# tea_maker.net
KiCad netlist of a schematic drawn in EAGLE
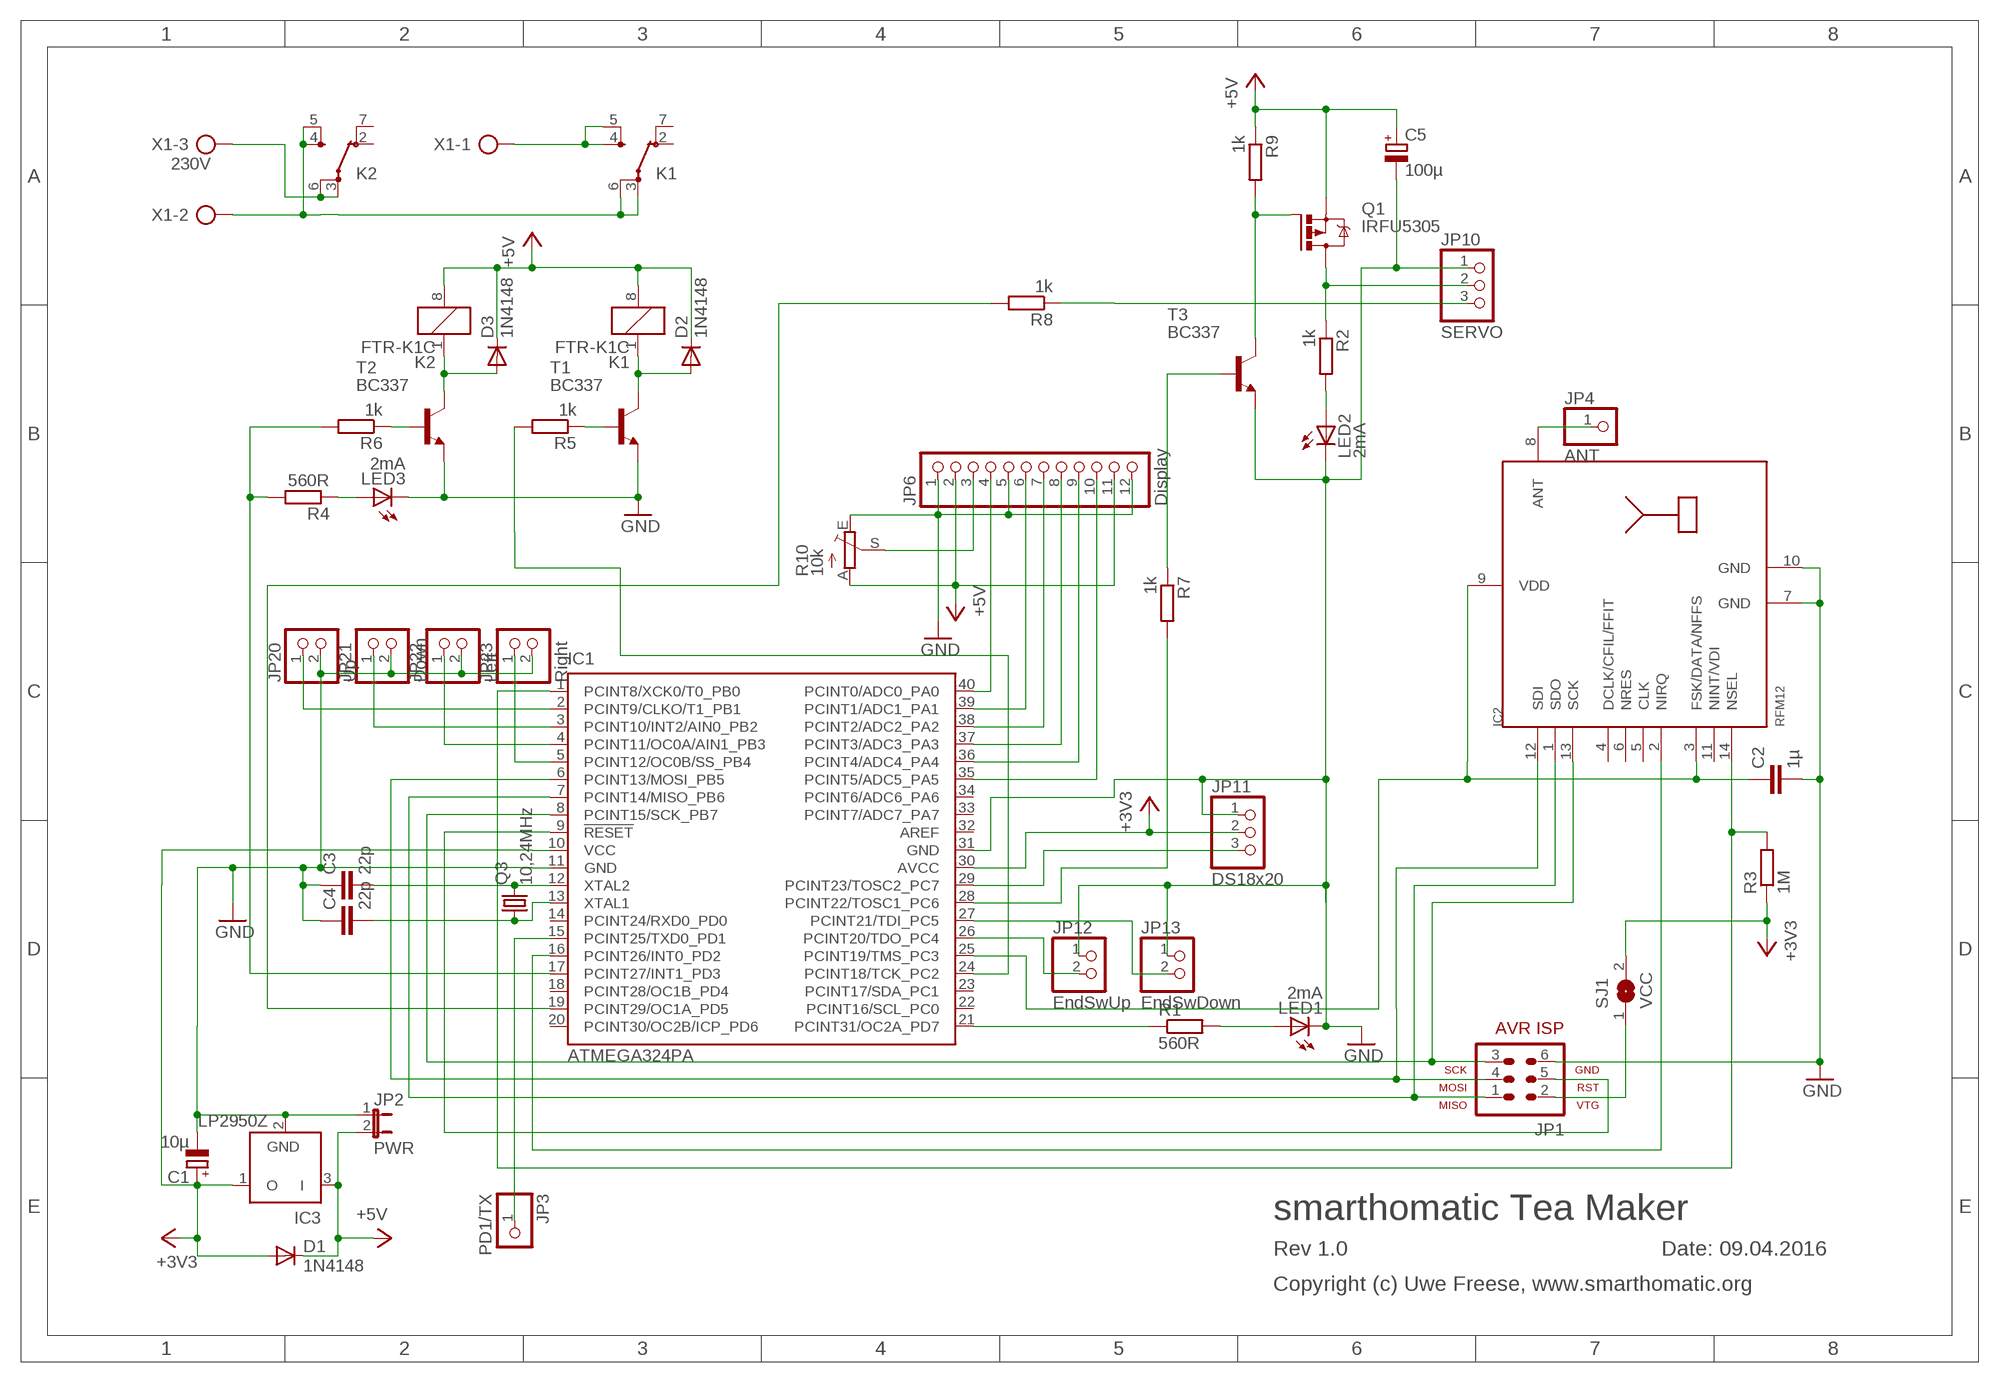
[diagram p0: schematic, sheet 1]

(export (version "E")
  (design (tool "Eeschema 10.0.6"))
  (components
    (comp (ref "C1")
      (value "10µ")
      (footprint "eagle-import:E1,8-4")
      (libsource (lib "eagle-import") (part "CPOL-EUE1.8-4"))
    )
    (comp (ref "C2")
      (value "1µ")
      (footprint "eagle-import:C5B3.5")
      (libsource (lib "eagle-import") (part "C5/3.5"))
    )
    (comp (ref "C3")
      (value "22p")
      (footprint "eagle-import:C025-024X044")
      (libsource (lib "eagle-import") (part "C-EU025-024X044"))
    )
    (comp (ref "C4")
      (value "22p")
      (footprint "eagle-import:C025-024X044")
      (libsource (lib "eagle-import") (part "C-EU025-024X044"))
    )
    (comp (ref "C5")
      (value "100µ")
      (footprint "eagle-import:E2,5-7")
      (libsource (lib "eagle-import") (part "CPOL-EUE2.5-7"))
    )
    (comp (ref "D1")
      (value "1N4148")
      (footprint "eagle-import:DO35-7")
      (libsource (lib "eagle-import") (part "1N4148DO35-7"))
    )
    (comp (ref "D2")
      (value "1N4148")
      (footprint "eagle-import:DO35-7")
      (libsource (lib "eagle-import") (part "1N4148DO35-7"))
    )
    (comp (ref "D3")
      (value "1N4148")
      (footprint "eagle-import:DO35-7")
      (libsource (lib "eagle-import") (part "1N4148DO35-7"))
    )
    (comp (ref "IC1")
      (value "ATMEGA324PA")
      (footprint "eagle-import:DIL40")
      (fields (field (name "MPN") "ATMEGA644V-10PU"))
      (libsource (lib "eagle-import") (part "ATMEGA644-PU10"))
    )
    (comp (ref "IC2")
      (value "RFM12")
      (footprint "eagle-import:RFM")
      (libsource (lib "eagle-import") (part "RFM12"))
    )
    (comp (ref "IC3")
      (value "LP2950Z")
      (footprint "eagle-import:TO92")
      (libsource (lib "eagle-import") (part "LP2950Z"))
    )
    (comp (ref "JP1")
      (value "AVR-ISP-6")
      (footprint "eagle-import:AVR-ISP-6")
      (libsource (lib "eagle-import") (part "AVR-ISP-6"))
    )
    (comp (ref "JP2")
      (value "PWR")
      (footprint "eagle-import:JP1")
      (libsource (lib "eagle-import") (part "JP1E"))
    )
    (comp (ref "JP3")
      (value "PD1/TX")
      (footprint "eagle-import:1X01")
      (libsource (lib "eagle-import") (part "PINHD-1X1"))
    )
    (comp (ref "JP4")
      (value "ANT")
      (footprint "eagle-import:1X01")
      (libsource (lib "eagle-import") (part "PINHD-1X1"))
    )
    (comp (ref "JP6")
      (value "Display")
      (footprint "eagle-import:1X12")
      (libsource (lib "eagle-import") (part "PINHD-1X12"))
    )
    (comp (ref "JP10")
      (value "SERVO")
      (footprint "eagle-import:1X03")
      (libsource (lib "eagle-import") (part "PINHD-1X3"))
    )
    (comp (ref "JP11")
      (value "DS18x20")
      (footprint "eagle-import:1X03")
      (libsource (lib "eagle-import") (part "PINHD-1X3"))
    )
    (comp (ref "JP12")
      (value "EndSwUp")
      (footprint "eagle-import:1X02")
      (libsource (lib "eagle-import") (part "PINHD-1X2"))
    )
    (comp (ref "JP13")
      (value "EndSwDown")
      (footprint "eagle-import:1X02")
      (libsource (lib "eagle-import") (part "PINHD-1X2"))
    )
    (comp (ref "JP20")
      (value "Up")
      (footprint "eagle-import:1X02")
      (libsource (lib "eagle-import") (part "PINHD-1X2"))
    )
    (comp (ref "JP21")
      (value "Down")
      (footprint "eagle-import:1X02")
      (libsource (lib "eagle-import") (part "PINHD-1X2"))
    )
    (comp (ref "JP22")
      (value "Left")
      (footprint "eagle-import:1X02")
      (libsource (lib "eagle-import") (part "PINHD-1X2"))
    )
    (comp (ref "JP23")
      (value "Right")
      (footprint "eagle-import:1X02")
      (libsource (lib "eagle-import") (part "PINHD-1X2"))
    )
    (comp (ref "K1")
      (value "FTR-K1C")
      (footprint "eagle-import:FTR-K1C")
      (libsource (lib "eagle-import") (part "FTR-K1C"))
    )
    (comp (ref "K2")
      (value "FTR-K1C")
      (footprint "eagle-import:FTR-K1C")
      (libsource (lib "eagle-import") (part "FTR-K1C"))
    )
    (comp (ref "LED1")
      (value "2mA")
      (footprint "eagle-import:LED3MM")
      (libsource (lib "eagle-import") (part "LED3MM"))
    )
    (comp (ref "LED2")
      (value "2mA")
      (footprint "eagle-import:LED3MM")
      (libsource (lib "eagle-import") (part "LED3MM"))
    )
    (comp (ref "LED3")
      (value "2mA")
      (footprint "eagle-import:LED3MM")
      (libsource (lib "eagle-import") (part "LED3MM"))
    )
    (comp (ref "Q1")
      (value "IRFU5305")
      (footprint "eagle-import:I-PAK_TO251AA")
      (libsource (lib "eagle-import") (part "IRF?5305U"))
    )
    (comp (ref "Q3")
      (value "10,24MHz")
      (footprint "eagle-import:HC49_S")
      (libsource (lib "eagle-import") (part "CRYSTALHC49S"))
    )
    (comp (ref "R1")
      (value "560R")
      (footprint "eagle-import:0207_7")
      (libsource (lib "eagle-import") (part "R-EU_0207/7"))
    )
    (comp (ref "R2")
      (value "1k")
      (footprint "eagle-import:0207_7")
      (libsource (lib "eagle-import") (part "R-EU_0207/7"))
    )
    (comp (ref "R3")
      (value "1M")
      (footprint "eagle-import:0207_7")
      (libsource (lib "eagle-import") (part "R-EU_0207/7"))
    )
    (comp (ref "R4")
      (value "560R")
      (footprint "eagle-import:0207_7")
      (libsource (lib "eagle-import") (part "R-EU_0207/7"))
    )
    (comp (ref "R5")
      (value "1k")
      (footprint "eagle-import:0207_7")
      (libsource (lib "eagle-import") (part "R-EU_0207/7"))
    )
    (comp (ref "R6")
      (value "1k")
      (footprint "eagle-import:0207_7")
      (libsource (lib "eagle-import") (part "R-EU_0207/7"))
    )
    (comp (ref "R7")
      (value "1k")
      (footprint "eagle-import:0207_7")
      (libsource (lib "eagle-import") (part "R-EU_0207/7"))
    )
    (comp (ref "R8")
      (value "1k")
      (footprint "eagle-import:0207_7")
      (libsource (lib "eagle-import") (part "R-EU_0207/7"))
    )
    (comp (ref "R9")
      (value "1k")
      (footprint "eagle-import:0207_7")
      (libsource (lib "eagle-import") (part "R-EU_0207/7"))
    )
    (comp (ref "R10")
      (value "10k")
      (footprint "eagle-import:PT-10S")
      (libsource (lib "eagle-import") (part "TRIM_EU-PT10S"))
    )
    (comp (ref "SJ1")
      (value "VCC")
      (footprint "eagle-import:SJ")
      (libsource (lib "eagle-import") (part "SJ"))
    )
    (comp (ref "T1")
      (value "BC337")
      (footprint "eagle-import:TO92")
      (libsource (lib "eagle-import") (part "BC337"))
    )
    (comp (ref "T2")
      (value "BC337")
      (footprint "eagle-import:TO92")
      (libsource (lib "eagle-import") (part "BC337"))
    )
    (comp (ref "T3")
      (value "BC337")
      (footprint "eagle-import:TO92")
      (libsource (lib "eagle-import") (part "BC337"))
    )
    (comp (ref "X1")
      (value "230V")
      (footprint "eagle-import:AK500_3")
      (libsource (lib "eagle-import") (part "AK500/3"))
    )
  )
  (nets
    (net (code "1") (name "+3V3") (class "Default")
      (node (ref "C1") (pin "+") (pinfunction "+_+") (pintype "passive"))
      (node (ref "D1") (pin "A") (pinfunction "A_A") (pintype "passive"))
      (node (ref "IC1") (pin "10") (pinfunction "VCC_10") (pintype "power_in"))
      (node (ref "IC1") (pin "30") (pinfunction "AVCC_30") (pintype "power_in"))
      (node (ref "IC3") (pin "1") (pinfunction "O_1") (pintype "input"))
      (node (ref "JP11") (pin "2") (pinfunction "2_2") (pintype "passive"))
      (node (ref "R3") (pin "1") (pinfunction "1_1") (pintype "passive"))
      (node (ref "SJ1") (pin "2") (pinfunction "2_2") (pintype "passive"))
    )
    (net (code "2") (name "+5V") (class "Default")
      (node (ref "C5") (pin "+") (pinfunction "+_+") (pintype "passive"))
      (node (ref "D1") (pin "C") (pinfunction "C_C") (pintype "passive"))
      (node (ref "D2") (pin "C") (pinfunction "C_C") (pintype "passive"))
      (node (ref "D3") (pin "C") (pinfunction "C_C") (pintype "passive"))
      (node (ref "IC3") (pin "3") (pinfunction "I_3") (pintype "input"))
      (node (ref "JP2") (pin "2") (pinfunction "2_2") (pintype "passive"))
      (node (ref "JP6") (pin "11") (pinfunction "11_11") (pintype "passive"))
      (node (ref "JP6") (pin "2") (pinfunction "2_2") (pintype "passive"))
      (node (ref "K1") (pin "8") (pinfunction "2_8") (pintype "passive"))
      (node (ref "K2") (pin "8") (pinfunction "2_8") (pintype "passive"))
      (node (ref "Q1") (pin "3") (pinfunction "S_3") (pintype "passive"))
      (node (ref "R10") (pin "A") (pinfunction "A_A") (pintype "passive"))
      (node (ref "R9") (pin "1") (pinfunction "1_1") (pintype "passive"))
    )
    (net (code "3") (name "GND") (class "Default")
      (node (ref "C1") (pin "-") (pinfunction "-_-") (pintype "passive"))
      (node (ref "C2") (pin "2") (pinfunction "2_2") (pintype "passive"))
      (node (ref "C3") (pin "1") (pinfunction "1_1") (pintype "passive"))
      (node (ref "C4") (pin "1") (pinfunction "1_1") (pintype "passive"))
      (node (ref "C5") (pin "-") (pinfunction "-_-") (pintype "passive"))
      (node (ref "IC1") (pin "11") (pinfunction "GND_11") (pintype "power_in"))
      (node (ref "IC1") (pin "31") (pinfunction "GND_31") (pintype "power_in"))
      (node (ref "IC2") (pin "10") (pinfunction "GND_10") (pintype "power_in"))
      (node (ref "IC2") (pin "7") (pinfunction "GND_7") (pintype "power_in"))
      (node (ref "IC3") (pin "2") (pinfunction "GND_2") (pintype "power_in"))
      (node (ref "JP1") (pin "6") (pinfunction "6_6") (pintype "passive"))
      (node (ref "JP10") (pin "1") (pinfunction "1_1") (pintype "passive"))
      (node (ref "JP11") (pin "1") (pinfunction "1_1") (pintype "passive"))
      (node (ref "JP12") (pin "1") (pinfunction "1_1") (pintype "passive"))
      (node (ref "JP13") (pin "1") (pinfunction "1_1") (pintype "passive"))
      (node (ref "JP2") (pin "1") (pinfunction "1_1") (pintype "passive"))
      (node (ref "JP20") (pin "2") (pinfunction "2_2") (pintype "passive"))
      (node (ref "JP21") (pin "2") (pinfunction "2_2") (pintype "passive"))
      (node (ref "JP22") (pin "2") (pinfunction "2_2") (pintype "passive"))
      (node (ref "JP23") (pin "2") (pinfunction "2_2") (pintype "passive"))
      (node (ref "JP6") (pin "1") (pinfunction "1_1") (pintype "passive"))
      (node (ref "JP6") (pin "12") (pinfunction "12_12") (pintype "passive"))
      (node (ref "JP6") (pin "5") (pinfunction "5_5") (pintype "passive"))
      (node (ref "LED1") (pin "K") (pinfunction "C_K") (pintype "passive"))
      (node (ref "LED2") (pin "K") (pinfunction "C_K") (pintype "passive"))
      (node (ref "LED3") (pin "K") (pinfunction "C_K") (pintype "passive"))
      (node (ref "R10") (pin "E") (pinfunction "E_E") (pintype "passive"))
      (node (ref "T1") (pin "1") (pinfunction "E_1") (pintype "passive"))
      (node (ref "T2") (pin "1") (pinfunction "E_1") (pintype "passive"))
      (node (ref "T3") (pin "1") (pinfunction "E_1") (pintype "passive"))
    )
    (net (code "4") (name "Net-(IC1-PCINT0{slash}ADC0_PA0)") (class "Default")
      (node (ref "IC1") (pin "40") (pinfunction "PCINT0/ADC0_PA0_40") (pintype "bidirectional"))
      (node (ref "JP6") (pin "4") (pinfunction "4_4") (pintype "passive"))
    )
    (net (code "5") (name "Net-(IC1-PCINT1{slash}ADC1_PA1)") (class "Default")
      (node (ref "IC1") (pin "39") (pinfunction "PCINT1/ADC1_PA1_39") (pintype "bidirectional"))
      (node (ref "JP6") (pin "6") (pinfunction "6_6") (pintype "passive"))
    )
    (net (code "6") (name "Net-(IC1-PCINT2{slash}ADC2_PA2)") (class "Default")
      (node (ref "IC1") (pin "38") (pinfunction "PCINT2/ADC2_PA2_38") (pintype "bidirectional"))
      (node (ref "JP6") (pin "7") (pinfunction "7_7") (pintype "passive"))
    )
    (net (code "7") (name "Net-(IC1-PCINT3{slash}ADC3_PA3)") (class "Default")
      (node (ref "IC1") (pin "37") (pinfunction "PCINT3/ADC3_PA3_37") (pintype "bidirectional"))
      (node (ref "JP6") (pin "8") (pinfunction "8_8") (pintype "passive"))
    )
    (net (code "8") (name "Net-(IC1-PCINT4{slash}ADC4_PA4)") (class "Default")
      (node (ref "IC1") (pin "36") (pinfunction "PCINT4/ADC4_PA4_36") (pintype "bidirectional"))
      (node (ref "JP6") (pin "9") (pinfunction "9_9") (pintype "passive"))
    )
    (net (code "9") (name "Net-(IC1-PCINT5{slash}ADC5_PA5)") (class "Default")
      (node (ref "IC1") (pin "35") (pinfunction "PCINT5/ADC5_PA5_35") (pintype "bidirectional"))
      (node (ref "JP6") (pin "10") (pinfunction "10_10") (pintype "passive"))
    )
    (net (code "10") (name "Net-(IC1-PCINT8{slash}XCK0{slash}T0_PB0)") (class "Default")
      (node (ref "IC1") (pin "1") (pinfunction "PCINT8/XCK0/T0_PB0_1") (pintype "bidirectional"))
      (node (ref "IC2") (pin "14") (pinfunction "NSEL_14") (pintype "bidirectional"))
      (node (ref "R3") (pin "2") (pinfunction "2_2") (pintype "passive"))
    )
    (net (code "11") (name "Net-(IC1-PCINT9{slash}CLKO{slash}T1_PB1)") (class "Default")
      (node (ref "IC1") (pin "2") (pinfunction "PCINT9/CLKO/T1_PB1_2") (pintype "bidirectional"))
      (node (ref "JP20") (pin "1") (pinfunction "1_1") (pintype "passive"))
    )
    (net (code "12") (name "Net-(IC1-PCINT10{slash}INT2{slash}AIN0_PB2)") (class "Default")
      (node (ref "IC1") (pin "3") (pinfunction "PCINT10/INT2/AIN0_PB2_3") (pintype "bidirectional"))
      (node (ref "JP21") (pin "1") (pinfunction "1_1") (pintype "passive"))
    )
    (net (code "13") (name "Net-(IC1-PCINT11{slash}OC0A{slash}AIN1_PB3)") (class "Default")
      (node (ref "IC1") (pin "4") (pinfunction "PCINT11/OC0A/AIN1_PB3_4") (pintype "bidirectional"))
      (node (ref "JP22") (pin "1") (pinfunction "1_1") (pintype "passive"))
    )
    (net (code "14") (name "Net-(IC1-PCINT12{slash}OC0B{slash}SS_PB4)") (class "Default")
      (node (ref "IC1") (pin "5") (pinfunction "PCINT12/OC0B/SS_PB4_5") (pintype "bidirectional"))
      (node (ref "JP23") (pin "1") (pinfunction "1_1") (pintype "passive"))
    )
    (net (code "15") (name "Net-(IC1-PCINT13{slash}MOSI_PB5)") (class "Default")
      (node (ref "IC1") (pin "6") (pinfunction "PCINT13/MOSI_PB5_6") (pintype "bidirectional"))
      (node (ref "IC2") (pin "12") (pinfunction "SDI_12") (pintype "bidirectional"))
      (node (ref "JP1") (pin "4") (pinfunction "4_4") (pintype "passive"))
    )
    (net (code "16") (name "Net-(IC1-PCINT14{slash}MISO_PB6)") (class "Default")
      (node (ref "IC1") (pin "7") (pinfunction "PCINT14/MISO_PB6_7") (pintype "bidirectional"))
      (node (ref "IC2") (pin "1") (pinfunction "SDO_1") (pintype "bidirectional"))
      (node (ref "JP1") (pin "1") (pinfunction "1_1") (pintype "passive"))
    )
    (net (code "17") (name "Net-(IC1-PCINT15{slash}SCK_PB7)") (class "Default")
      (node (ref "IC1") (pin "8") (pinfunction "PCINT15/SCK_PB7_8") (pintype "bidirectional"))
      (node (ref "IC2") (pin "13") (pinfunction "SCK_13") (pintype "bidirectional"))
      (node (ref "JP1") (pin "3") (pinfunction "3_3") (pintype "passive"))
    )
    (net (code "18") (name "Net-(IC1-PCINT18{slash}TCK_PC2)") (class "Default")
      (node (ref "IC1") (pin "24") (pinfunction "PCINT18/TCK_PC2_24") (pintype "bidirectional"))
      (node (ref "R5") (pin "2") (pinfunction "2_2") (pintype "passive"))
    )
    (net (code "19") (name "Net-(IC1-PCINT19{slash}TMS_PC3)") (class "Default")
      (node (ref "C2") (pin "1") (pinfunction "1_1") (pintype "passive"))
      (node (ref "IC1") (pin "25") (pinfunction "PCINT19/TMS_PC3_25") (pintype "bidirectional"))
      (node (ref "IC2") (pin "3") (pinfunction "FSK/DATA/NFFS_3") (pintype "bidirectional"))
      (node (ref "IC2") (pin "9") (pinfunction "VDD_9") (pintype "power_in"))
    )
    (net (code "20") (name "Net-(IC1-PCINT20{slash}TDO_PC4)") (class "Default")
      (node (ref "IC1") (pin "26") (pinfunction "PCINT20/TDO_PC4_26") (pintype "bidirectional"))
      (node (ref "JP12") (pin "2") (pinfunction "2_2") (pintype "passive"))
    )
    (net (code "21") (name "Net-(IC1-PCINT21{slash}TDI_PC5)") (class "Default")
      (node (ref "IC1") (pin "27") (pinfunction "PCINT21/TDI_PC5_27") (pintype "bidirectional"))
      (node (ref "JP13") (pin "2") (pinfunction "2_2") (pintype "passive"))
    )
    (net (code "22") (name "Net-(IC1-PCINT22{slash}TOSC1_PC6)") (class "Default")
      (node (ref "IC1") (pin "28") (pinfunction "PCINT22/TOSC1_PC6_28") (pintype "bidirectional"))
      (node (ref "R7") (pin "2") (pinfunction "2_2") (pintype "passive"))
    )
    (net (code "23") (name "Net-(IC1-PCINT23{slash}TOSC2_PC7)") (class "Default")
      (node (ref "IC1") (pin "29") (pinfunction "PCINT23/TOSC2_PC7_29") (pintype "bidirectional"))
      (node (ref "JP11") (pin "3") (pinfunction "3_3") (pintype "passive"))
    )
    (net (code "24") (name "Net-(IC1-PCINT25{slash}TXD0_PD1)") (class "Default")
      (node (ref "IC1") (pin "15") (pinfunction "PCINT25/TXD0_PD1_15") (pintype "bidirectional"))
      (node (ref "JP3") (pin "1") (pinfunction "1_1") (pintype "passive"))
    )
    (net (code "25") (name "Net-(IC1-PCINT26{slash}INT0_PD2)") (class "Default")
      (node (ref "IC1") (pin "16") (pinfunction "PCINT26/INT0_PD2_16") (pintype "bidirectional"))
      (node (ref "IC2") (pin "2") (pinfunction "NIRQ_2") (pintype "bidirectional"))
    )
    (net (code "26") (name "Net-(IC1-PCINT27{slash}INT1_PD3)") (class "Default")
      (node (ref "IC1") (pin "17") (pinfunction "PCINT27/INT1_PD3_17") (pintype "bidirectional"))
      (node (ref "R4") (pin "2") (pinfunction "2_2") (pintype "passive"))
      (node (ref "R6") (pin "2") (pinfunction "2_2") (pintype "passive"))
    )
    (net (code "27") (name "Net-(IC1-PCINT29{slash}OC1A_PD5)") (class "Default")
      (node (ref "IC1") (pin "19") (pinfunction "PCINT29/OC1A_PD5_19") (pintype "bidirectional"))
      (node (ref "R8") (pin "2") (pinfunction "2_2") (pintype "passive"))
    )
    (net (code "28") (name "Net-(IC1-PCINT31{slash}OC2A_PD7)") (class "Default")
      (node (ref "IC1") (pin "21") (pinfunction "PCINT31/OC2A_PD7_21") (pintype "bidirectional"))
      (node (ref "R1") (pin "1") (pinfunction "1_1") (pintype "passive"))
    )
    (net (code "29") (name "Net-(IC1-XTAL1)") (class "Default")
      (node (ref "C4") (pin "2") (pinfunction "2_2") (pintype "passive"))
      (node (ref "IC1") (pin "13") (pinfunction "XTAL1_13") (pintype "input"))
      (node (ref "Q3") (pin "1") (pinfunction "1_1") (pintype "passive"))
    )
    (net (code "30") (name "Net-(IC1-XTAL2)") (class "Default")
      (node (ref "C3") (pin "2") (pinfunction "2_2") (pintype "passive"))
      (node (ref "IC1") (pin "12") (pinfunction "XTAL2_12") (pintype "output"))
      (node (ref "Q3") (pin "2") (pinfunction "2_2") (pintype "passive"))
    )
    (net (code "31") (name "Net-(IC1-~{RESET})") (class "Default")
      (node (ref "IC1") (pin "9") (pinfunction "~{RESET}_9") (pintype "input"))
      (node (ref "JP1") (pin "5") (pinfunction "5_5") (pintype "passive"))
    )
    (net (code "32") (name "Net-(IC2-ANT)") (class "Default")
      (node (ref "IC2") (pin "8") (pinfunction "ANT_8") (pintype "output"))
      (node (ref "JP4") (pin "1") (pinfunction "1_1") (pintype "passive"))
    )
    (net (code "33") (name "Net-(JP1-Pad2)") (class "Default")
      (node (ref "JP1") (pin "2") (pinfunction "2_2") (pintype "passive"))
      (node (ref "SJ1") (pin "1") (pinfunction "1_1") (pintype "passive"))
    )
    (net (code "34") (name "Net-(JP6-Pad3)") (class "Default")
      (node (ref "JP6") (pin "3") (pinfunction "3_3") (pintype "passive"))
      (node (ref "R10") (pin "S") (pinfunction "S_S") (pintype "passive"))
    )
    (net (code "35") (name "Net-(JP10-Pad3)") (class "Default")
      (node (ref "JP10") (pin "3") (pinfunction "3_3") (pintype "passive"))
      (node (ref "R8") (pin "1") (pinfunction "1_1") (pintype "passive"))
    )
    (net (code "36") (name "Net-(K1A-PA)") (class "Default")
      (node (ref "K1") (pin "3") (pinfunction "PA_3") (pintype "passive"))
      (node (ref "K1") (pin "6") (pinfunction "PB_6") (pintype "passive"))
      (node (ref "K2") (pin "4") (pinfunction "SA_4") (pintype "passive"))
      (node (ref "K2") (pin "5") (pinfunction "SB_5") (pintype "passive"))
      (node (ref "X1") (pin "2") (pinfunction "KL_2") (pintype "passive"))
    )
    (net (code "37") (name "Net-(K1A-SA)") (class "Default")
      (node (ref "K1") (pin "4") (pinfunction "SA_4") (pintype "passive"))
      (node (ref "K1") (pin "5") (pinfunction "SB_5") (pintype "passive"))
      (node (ref "X1") (pin "1") (pinfunction "KL_1") (pintype "passive"))
    )
    (net (code "38") (name "Net-(K2A-PA)") (class "Default")
      (node (ref "K2") (pin "3") (pinfunction "PA_3") (pintype "passive"))
      (node (ref "K2") (pin "6") (pinfunction "PB_6") (pintype "passive"))
      (node (ref "X1") (pin "3") (pinfunction "KL_3") (pintype "passive"))
    )
    (net (code "39") (name "Net-(LED1-PadA)") (class "Default")
      (node (ref "LED1") (pin "A") (pinfunction "A_A") (pintype "passive"))
      (node (ref "R1") (pin "2") (pinfunction "2_2") (pintype "passive"))
    )
    (net (code "40") (name "Net-(LED2-PadA)") (class "Default")
      (node (ref "LED2") (pin "A") (pinfunction "A_A") (pintype "passive"))
      (node (ref "R2") (pin "2") (pinfunction "2_2") (pintype "passive"))
    )
    (net (code "41") (name "Net-(LED3-PadA)") (class "Default")
      (node (ref "LED3") (pin "A") (pinfunction "A_A") (pintype "passive"))
      (node (ref "R4") (pin "1") (pinfunction "1_1") (pintype "passive"))
    )
    (net (code "42") (name "Net-(Q1-D)") (class "Default")
      (node (ref "JP10") (pin "2") (pinfunction "2_2") (pintype "passive"))
      (node (ref "Q1") (pin "2") (pinfunction "D_2") (pintype "passive"))
      (node (ref "R2") (pin "1") (pinfunction "1_1") (pintype "passive"))
    )
    (net (code "43") (name "Net-(Q1-G)") (class "Default")
      (node (ref "Q1") (pin "1") (pinfunction "G_1") (pintype "passive"))
      (node (ref "R9") (pin "2") (pinfunction "2_2") (pintype "passive"))
      (node (ref "T3") (pin "3") (pinfunction "C_3") (pintype "passive"))
    )
    (net (code "44") (name "Net-(T1-B)") (class "Default")
      (node (ref "R5") (pin "1") (pinfunction "1_1") (pintype "passive"))
      (node (ref "T1") (pin "2") (pinfunction "B_2") (pintype "passive"))
    )
    (net (code "45") (name "Net-(T1-C)") (class "Default")
      (node (ref "D2") (pin "A") (pinfunction "A_A") (pintype "passive"))
      (node (ref "K1") (pin "1") (pinfunction "1_1") (pintype "passive"))
      (node (ref "T1") (pin "3") (pinfunction "C_3") (pintype "passive"))
    )
    (net (code "46") (name "Net-(T2-B)") (class "Default")
      (node (ref "R6") (pin "1") (pinfunction "1_1") (pintype "passive"))
      (node (ref "T2") (pin "2") (pinfunction "B_2") (pintype "passive"))
    )
    (net (code "47") (name "Net-(T2-C)") (class "Default")
      (node (ref "D3") (pin "A") (pinfunction "A_A") (pintype "passive"))
      (node (ref "K2") (pin "1") (pinfunction "1_1") (pintype "passive"))
      (node (ref "T2") (pin "3") (pinfunction "C_3") (pintype "passive"))
    )
    (net (code "48") (name "Net-(T3-B)") (class "Default")
      (node (ref "R7") (pin "1") (pinfunction "1_1") (pintype "passive"))
      (node (ref "T3") (pin "2") (pinfunction "B_2") (pintype "passive"))
    )
    (net (code "49") (name "unconnected-(IC1-AREF-Pad32)") (class "Default")
      (node (ref "IC1") (pin "32") (pinfunction "AREF_32") (pintype "passive"))
    )
    (net (code "50") (name "unconnected-(IC1-PCINT6{slash}ADC6_PA6-Pad34)") (class "Default")
      (node (ref "IC1") (pin "34") (pinfunction "PCINT6/ADC6_PA6_34") (pintype "bidirectional"))
    )
    (net (code "51") (name "unconnected-(IC1-PCINT7{slash}ADC7_PA7-Pad33)") (class "Default")
      (node (ref "IC1") (pin "33") (pinfunction "PCINT7/ADC7_PA7_33") (pintype "bidirectional"))
    )
    (net (code "52") (name "unconnected-(IC1-PCINT16{slash}SCL_PC0-Pad22)") (class "Default")
      (node (ref "IC1") (pin "22") (pinfunction "PCINT16/SCL_PC0_22") (pintype "bidirectional"))
    )
    (net (code "53") (name "unconnected-(IC1-PCINT17{slash}SDA_PC1-Pad23)") (class "Default")
      (node (ref "IC1") (pin "23") (pinfunction "PCINT17/SDA_PC1_23") (pintype "bidirectional"))
    )
    (net (code "54") (name "unconnected-(IC1-PCINT24{slash}RXD0_PD0-Pad14)") (class "Default")
      (node (ref "IC1") (pin "14") (pinfunction "PCINT24/RXD0_PD0_14") (pintype "bidirectional"))
    )
    (net (code "55") (name "unconnected-(IC1-PCINT28{slash}OC1B_PD4-Pad18)") (class "Default")
      (node (ref "IC1") (pin "18") (pinfunction "PCINT28/OC1B_PD4_18") (pintype "bidirectional"))
    )
    (net (code "56") (name "unconnected-(IC1-PCINT30{slash}OC2B{slash}ICP_PD6-Pad20)") (class "Default")
      (node (ref "IC1") (pin "20") (pinfunction "PCINT30/OC2B/ICP_PD6_20") (pintype "bidirectional"))
    )
    (net (code "57") (name "unconnected-(IC2-CLK-Pad5)") (class "Default")
      (node (ref "IC2") (pin "5") (pinfunction "CLK_5") (pintype "bidirectional"))
    )
    (net (code "58") (name "unconnected-(IC2-DCLK{slash}CFIL{slash}FFIT-Pad4)") (class "Default")
      (node (ref "IC2") (pin "4") (pinfunction "DCLK/CFIL/FFIT_4") (pintype "bidirectional"))
    )
    (net (code "59") (name "unconnected-(IC2-NINT{slash}VDI-Pad11)") (class "Default")
      (node (ref "IC2") (pin "11") (pinfunction "NINT/VDI_11") (pintype "bidirectional"))
    )
    (net (code "60") (name "unconnected-(IC2-NRES-Pad6)") (class "Default")
      (node (ref "IC2") (pin "6") (pinfunction "NRES_6") (pintype "bidirectional"))
    )
    (net (code "61") (name "unconnected-(K1A-OA-Pad2)") (class "Default")
      (node (ref "K1") (pin "2") (pinfunction "OA_2") (pintype "passive"))
    )
    (net (code "62") (name "unconnected-(K1A-OB-Pad7)") (class "Default")
      (node (ref "K1") (pin "7") (pinfunction "OB_7") (pintype "passive"))
    )
    (net (code "63") (name "unconnected-(K2A-OA-Pad2)") (class "Default")
      (node (ref "K2") (pin "2") (pinfunction "OA_2") (pintype "passive"))
    )
    (net (code "64") (name "unconnected-(K2A-OB-Pad7)") (class "Default")
      (node (ref "K2") (pin "7") (pinfunction "OB_7") (pintype "passive"))
    )
  )
)
